# WX0_011_442DL.net
KiCad netlist of a schematic drawn in Altium Designer
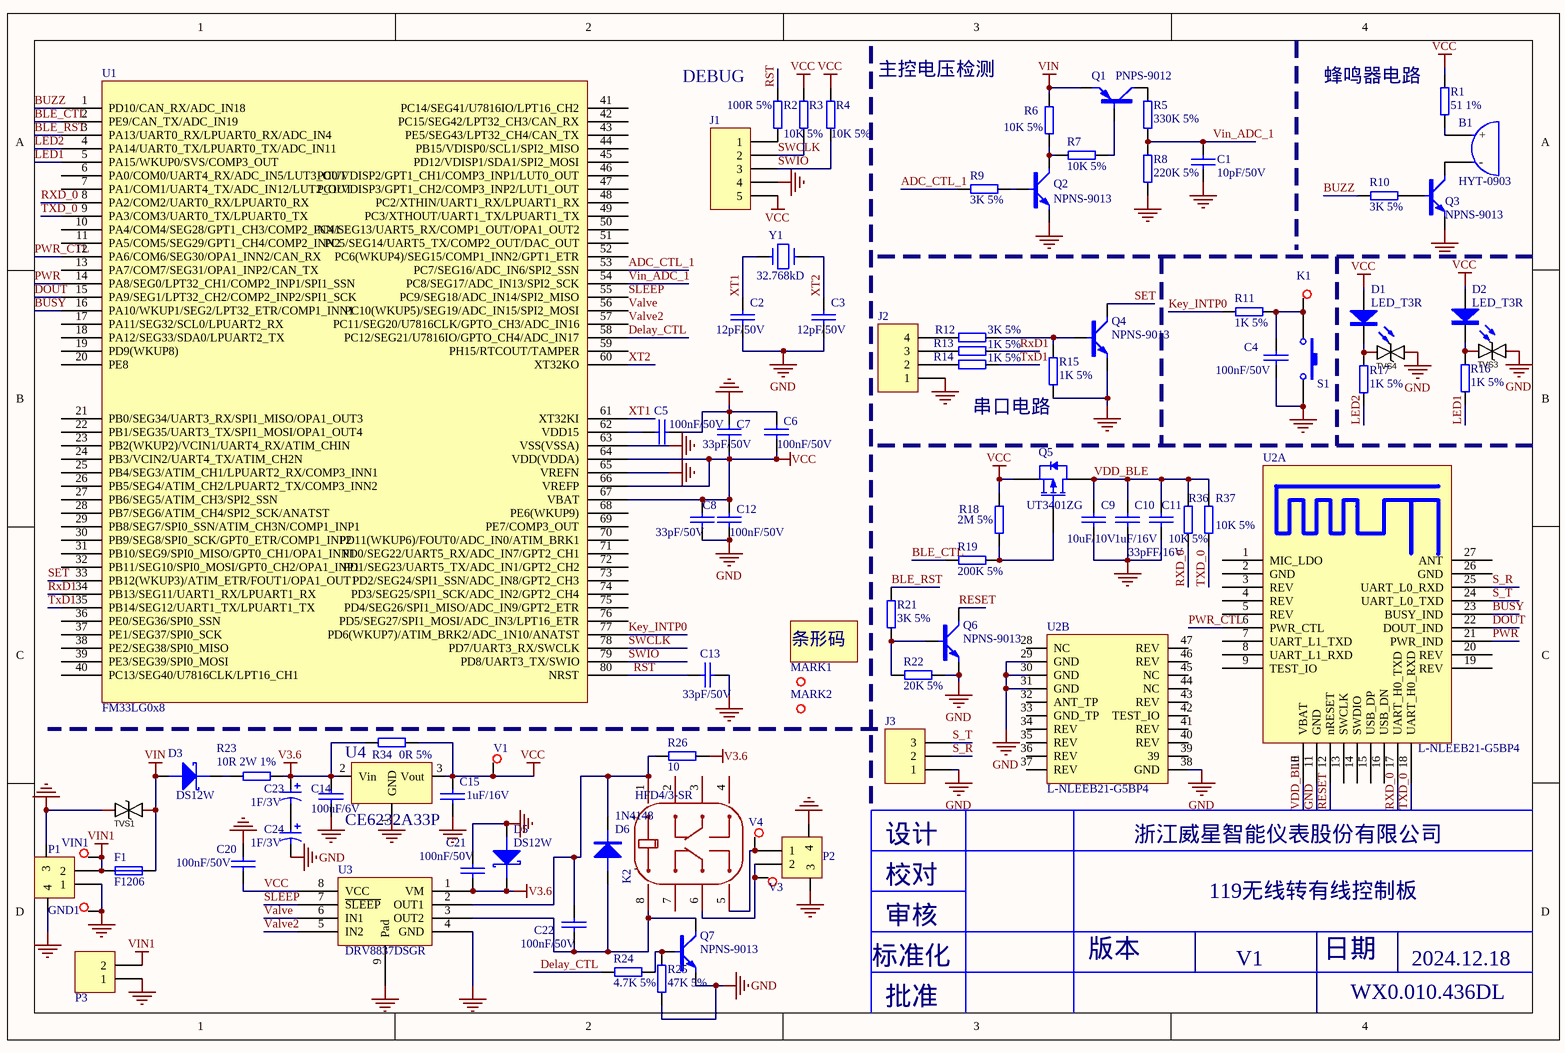
[diagram p0: WX0.011.442DL.SchDoc]

(export (version "E")
  (design (tool "Eeschema 10.0.6"))
  (components
    (comp (ref "*1")
      (value "Bar Code1")
      (footprint "Bar Code1")
      (description "条形码 ,填充，无需焊接器件")
      (fields (field (name "PART NUMBER") "AD_WXHJ_Bar Code_02"))
      (libsource (lib "Database_Libs2") (part "05_AD_WXHJ_Bar Code_02"))
    )
    (comp (ref "B1")
      (value "HYT-0903")
      (footprint "HYT-0903")
      (description "直插,直径9mm,高5.5mm,5 V,2 V,30 mA,兴化市华宇电子有限公司,HYT-0903")
      (fields (field (name "PART NUMBER") "1010602-0007"))
      (libsource (lib "Database_Libs2") (part "07_HYT-0903"))
    )
    (comp (ref "C1")
      (value "10pF/50V")
      (footprint "CAP0603")
      (description "10pF,50 V,±5%,0603,X7R,国巨,CC0603JRNPO9BN100")
      (fields (field (name "PART NUMBER") "101020103-0014"))
      (libsource (lib "Database_Libs2") (part "CC03JPO9_10P"))
    )
    (comp (ref "C2")
      (value "12pF/50V")
      (footprint "CAP0603")
      (description "12P,50 V,±5%,0603,国巨,CC0603JRNPO9BN12")
      (fields (field (name "PART NUMBER") "101020103-0005"))
      (libsource (lib "Database_Libs2") (part "CC03JPO9_12P"))
    )
    (comp (ref "C3")
      (value "12pF/50V")
      (footprint "CAP0603")
      (description "12P,50 V,±5%,0603,国巨,CC0603JRNPO9BN12")
      (fields (field (name "PART NUMBER") "101020103-0005"))
      (libsource (lib "Database_Libs2") (part "CC03JPO9_12P"))
    )
    (comp (ref "C4")
      (value "100nF/50V")
      (footprint "CAP0603")
      (description "104pF,50 V,±10%,0603,国巨,CC0603KRX7R9BB104")
      (fields (field (name "PART NUMBER") "101020103-0021"))
      (libsource (lib "Database_Libs2") (part "CC03K7R9_100N"))
    )
    (comp (ref "C5")
      (value "100nF/50V")
      (footprint "CAP0603")
      (description "104pF,50 V,±10%,0603,国巨,CC0603KRX7R9BB104")
      (fields (field (name "PART NUMBER") "101020103-0021"))
      (libsource (lib "Database_Libs2") (part "CC03K7R9_100N"))
    )
    (comp (ref "C6")
      (value "100nF/50V")
      (footprint "CAP0603")
      (description "104pF,50 V,±10%,0603,国巨,CC0603KRX7R9BB104")
      (fields (field (name "PART NUMBER") "101020103-0021"))
      (libsource (lib "Database_Libs2") (part "CC03K7R9_100N"))
    )
    (comp (ref "C7")
      (value "33pF/50V")
      (footprint "CAP0603")
      (description "33pF,50 V,±10%,0603,国巨,CC0603KRNPO9BN33")
      (fields (field (name "PART NUMBER") "101020103-0027"))
      (libsource (lib "Database_Libs2") (part "CC03KPO9_33P"))
    )
    (comp (ref "C8")
      (value "33pF/50V")
      (footprint "CAP0603")
      (description "33pF,50 V,±10%,0603,国巨,CC0603KRNPO9BN33")
      (fields (field (name "PART NUMBER") "101020103-0027"))
      (libsource (lib "Database_Libs2") (part "CC03KPO9_33P"))
    )
    (comp (ref "C9")
      (value "10uF/10V")
      (footprint "CAP0603")
      (description "106pF,10 V,±10%,0603,村田,GRM188R61A106KE47D")
      (fields (field (name "PART NUMBER") "101020103-0026"))
      (libsource (lib "Database_Libs2") (part "CC03K5R6_10U"))
    )
    (comp (ref "C10")
      (value "1uF/16V")
      (footprint "CAP0603")
      (description "105pF,16 V,±10%,0603,国巨,CC0603KRX7R7BB105")
      (fields (field (name "PART NUMBER") "101020103-0003"))
      (libsource (lib "Database_Libs2") (part "CC03K7R7_1U"))
    )
    (comp (ref "C11")
      (value "33pFF/16V")
      (footprint "CAP0603")
      (description "105pF,16 V,±10%,0603,国巨,CC0603KRX7R7BB105")
      (fields (field (name "PART NUMBER") "101020103-0003"))
      (libsource (lib "Database_Libs2") (part "CC03K7R7_1U"))
    )
    (comp (ref "C12")
      (value "100nF/50V")
      (footprint "CAP0603")
      (description "104pF,50 V,±10%,0603,国巨,CC0603KRX7R9BB104")
      (fields (field (name "PART NUMBER") "101020103-0021"))
      (libsource (lib "Database_Libs2") (part "CC03K7R9_100N"))
    )
    (comp (ref "C13")
      (value "33pF/50V")
      (footprint "CAP0603")
      (description "33pF,50 V,±10%,0603,国巨,CC0603KRNPO9BN33")
      (fields (field (name "PART NUMBER") "101020103-0027"))
      (libsource (lib "Database_Libs2") (part "CC03KPO9_33P"))
    )
    (comp (ref "C14")
      (value "100uF/6V")
      (footprint "GRM1206")
      (description "226P,10 V,±20%,0805,村田电子有限公司,GRM21BR61A226ME51L")
      (fields (field (name "PART NUMBER") "101020102-0012"))
      (libsource (lib "Database_Libs2") (part "CC05M5R6_226P"))
    )
    (comp (ref "C15")
      (value "1uF/16V")
      (footprint "CAP0603")
      (description "105pF,16 V,±10%,0603,国巨,CC0603KRX7R7BB105")
      (fields (field (name "PART NUMBER") "101020103-0003"))
      (libsource (lib "Database_Libs2") (part "CC03K7R7_1U"))
    )
    (comp (ref "C20")
      (value "100nF/50V")
      (footprint "CAP0603")
      (description "104pF,50 V,±10%,0603,国巨,CC0603KRX7R9BB104")
      (fields (field (name "PART NUMBER") "101020103-0021"))
      (libsource (lib "Database_Libs2") (part "CC03K7R9_100N"))
    )
    (comp (ref "C21")
      (value "100nF/50V")
      (footprint "CAP0603")
      (description "104pF,50 V,±10%,0603,国巨,CC0603KRX7R9BB104")
      (fields (field (name "PART NUMBER") "101020103-0021"))
      (libsource (lib "Database_Libs2") (part "CC03K7R9_100N"))
    )
    (comp (ref "C22")
      (value "100nF/50V")
      (footprint "CAP0603")
      (description "104pF,50 V,±10%,0603,国巨,CC0603KRX7R9BB104")
      (fields (field (name "PART NUMBER") "101020103-0021"))
      (libsource (lib "Database_Libs2") (part "CC03K7R9_100N"))
    )
    (comp (ref "C23")
      (value "1F/3V")
      (footprint "CAPPC_350_800_1600R")
      (description "1F,2.75 V,-20%~+20%,8mm*16mm,红宝石,2.7 DMC 1 M MY4 8X16")
      (fields (field (name "PART NUMBER") "1010202-0015"))
      (libsource (lib "Database_Libs2") (part "CALM3MRDMC_1F"))
    )
    (comp (ref "C24")
      (value "1F/3V")
      (footprint "CAPPC_350_800_1600R")
      (description "1F,2.75 V,-20%~+20%,8mm*16mm,红宝石,2.7 DMC 1 M MY4 8X16")
      (fields (field (name "PART NUMBER") "1010202-0015"))
      (libsource (lib "Database_Libs2") (part "CALM3MRDMC_1F"))
    )
    (comp (ref "D1")
      (value "LED_T3R")
      (footprint "LED-SMD-0603 - SMT")
      (description "圆形插件,3mm 圆形,插件,红光,湖北匡通电子有限公司,3BB4HC")
      (fields (field (name "PART NUMBER") "101040102-0001"))
      (libsource (lib "Database_Libs2") (part "01-LED_T3R"))
    )
    (comp (ref "D2")
      (value "LED_T3R")
      (footprint "LED-SMD-0603 - SMT")
      (description "圆形插件,3mm 圆形,插件,红光,湖北匡通电子有限公司,3BB4HC")
      (fields (field (name "PART NUMBER") "101040102-0001"))
      (libsource (lib "Database_Libs2") (part "01-LED_T3R"))
    )
    (comp (ref "D3")
      (value "DS12W")
      (footprint "SOD-123FL")
      (description "DS36W,SOD123-FL,3 A,42 V,60 V,浙江领晨科技有限公司,DS36W")
      (fields (field (name "PART NUMBER") "101040101-0055"))
      (libsource (lib "Database_Libs2") (part "02_DS36W"))
    )
    (comp (ref "D5")
      (value "DS12W")
      (footprint "SOD-123FL")
      (description "DS36W,SOD123-FL,3 A,42 V,60 V,浙江领晨科技有限公司,DS36W")
      (fields (field (name "PART NUMBER") "101040101-0055"))
      (libsource (lib "Database_Libs2") (part "02_DS36W"))
    )
    (comp (ref "D6")
      (value "1N4148")
      (footprint "LL34")
      (description "二极管，Diode")
      (libsource (lib "CBB_Lib_SCH") (part "DIODE"))
    )
    (comp (ref "F1") (value "F1206") (footprint "RES1206") (libsource (lib "Resistor_WX") (part "F1206")))
    (comp (ref "GND1")
      (value "TEST-PAD")
      (footprint "TEST-PAD")
      (description "单面焊盘测试点")
      (fields (field (name "PART NUMBER") "AD_WXHJ_TEST-PAD_01"))
      (libsource (lib "Database_Libs2") (part "TEST-PAD"))
    )
    (comp (ref "J1")
      (value "PIN254_1*5*WXHJ")
      (footprint "PIN254_1*5SR")
      (description "1*5 ，Φ1.0 ，2.54mm，直脚,无需焊接器件")
      (fields (field (name "PART NUMBER") "AD_WXHJ_PinHeader_02"))
      (libsource (lib "Database_Libs2") (part "PIN254_1*5*WXHJ"))
    )
    (comp (ref "J2")
      (value "PIN254_1*4*WXHJ")
      (footprint "PIN254_1*4*1100S")
      (description "1*4 ，Φ1.0 ，2.54mm，直脚,无需焊接器件")
      (fields (field (name "PART NUMBER") "AD_WXHJ_PinHeader_01"))
      (libsource (lib "Database_Libs2") (part "PIN254_1*4*WXHJ"))
    )
    (comp (ref "J3")
      (value "PIN254_1*3")
      (footprint "PIN254_1*3*WXHJ")
      (libsource (lib "Connect_WX") (part "PIN254_1*3"))
    )
    (comp (ref "K1")
      (value "TEST-PAD")
      (footprint "TEST-PAD")
      (description "单面焊盘测试点")
      (fields (field (name "PART NUMBER") "AD_WXHJ_TEST-PAD_01"))
      (libsource (lib "Database_Libs2") (part "TEST-PAD"))
    )
    (comp (ref "K2")
      (value "HFD4/3-SR")
      (footprint "RELAY-SMD_HFD4-XX-SR")
      (fields (field (name "MANUFACTURER") "HF(宏发)"))
      (libsource (lib "altium-import") (part "root_2_mirrored_HFD4/3-SR_"))
    )
    (comp (ref "MARK1")
      (value "MARK")
      (footprint "MARK")
      (description "MARK点")
      (fields (field (name "PART NUMBER") "AD_WXHJ_MARK_01"))
      (libsource (lib "Database_Libs2") (part "MARK"))
    )
    (comp (ref "MARK2")
      (value "MARK")
      (footprint "MARK")
      (description "MARK点")
      (fields (field (name "PART NUMBER") "AD_WXHJ_MARK_01"))
      (libsource (lib "Database_Libs2") (part "MARK"))
    )
    (comp (ref "P1") (value "~") (footprint "2P_2.0mm") (libsource (lib "Connect_WX") (part "SMT_2.0_卧")))
    (comp (ref "P2") (value "~") (libsource (lib "") (part "SMT_2.0_卧_1")))
    (comp (ref "P3")
      (value "PH200_1*2R")
      (footprint "PH200_1*2R_BAT")
      (description "2.0-2AW,直插弯座，2PIN，脚间距2mm，带防翘起,公头,单排,2.0-2AW;直插弯座，2PIN,脚间距2mm，带防翘起")
      (fields (field (name "PART NUMBER") "1010902-0105"))
      (libsource (lib "Free Documents") (part "PH200_1*2R"))
    )
    (comp (ref "Q1")
      (value "PNPS-9012")
      (footprint "SOT-23")
      (description "9012,PNP,SOT-23,JCET;长电,S9012")
      (fields (field (name "PART NUMBER") "101040201-0001"))
      (libsource (lib "Database_Libs2") (part "03_PNPS-9012"))
    )
    (comp (ref "Q2")
      (value "NPNS-9013")
      (footprint "SOT-23")
      (description "9013,NPN,SOT-23,长电,S9013")
      (fields (field (name "PART NUMBER") "101040201-0002"))
      (libsource (lib "Database_Libs2") (part "03_NPNS-9013"))
    )
    (comp (ref "Q3")
      (value "NPNS-9013")
      (footprint "SOT-23")
      (description "9013,NPN,SOT-23,长电,S9013")
      (fields (field (name "PART NUMBER") "101040201-0002"))
      (libsource (lib "Database_Libs2") (part "03_NPNS-9013"))
    )
    (comp (ref "Q4")
      (value "NPNS-9013")
      (footprint "SOT-23")
      (description "9013,NPN,SOT-23,长电,S9013")
      (fields (field (name "PART NUMBER") "101040201-0002"))
      (libsource (lib "Database_Libs2") (part "03_NPNS-9013"))
    )
    (comp (ref "Q5")
      (value "UT3401ZG")
      (footprint "SOT-23")
      (description "UT3401ZG,P-MOS,SOT-23,UTC,UT3401ZG")
      (fields (field (name "PART NUMBER") "101040201-0013"))
      (libsource (lib "Database_Libs2") (part "03_P-UT3401ZG"))
    )
    (comp (ref "Q6")
      (value "NPNS-9013")
      (footprint "SOT-23")
      (description "9013,NPN,SOT-23,长电,S9013")
      (fields (field (name "PART NUMBER") "101040201-0002"))
      (libsource (lib "Database_Libs2") (part "03_NPNS-9013"))
    )
    (comp (ref "Q7")
      (value "NPNS-9013")
      (footprint "SOT-23")
      (description "9013,NPN,SOT-23,长电,S9013")
      (fields (field (name "PART NUMBER") "101040201-0002"))
      (libsource (lib "Database_Libs2") (part "03_NPNS-9013"))
    )
    (comp (ref "R1")
      (value "51 1%")
      (footprint "RES0603")
      (description "国巨,±5%,0603,,155 ℃,-55 ℃,RC0603JR-0751RL,无铅,100 ppm/℃,1/10W,,51欧")
      (fields (field (name "PART NUMBER") "101010103-0037"))
      (libsource (lib "Database_Libs2") (part "RC03J_51R"))
    )
    (comp (ref "R2")
      (value "100R 5%")
      (footprint "RES0603")
      (description "100R,±5%,1/10W,0603,国巨,RC0603JR-07100RL")
      (fields (field (name "PART NUMBER") "101010103-0022"))
      (libsource (lib "Database_Libs2") (part "RC03J_100R"))
    )
    (comp (ref "R3")
      (value "10K 5%")
      (footprint "RES0603")
      (description "国巨,±5%,0603,,155 ℃,-55 ℃,RC0603JR-0710KL,无铅,200 ppm/℃,1/10W,,10K")
      (fields (field (name "PART NUMBER") "101010103-0003"))
      (libsource (lib "Database_Libs2") (part "RC03J_10K"))
    )
    (comp (ref "R4")
      (value "10K 5%")
      (footprint "RES0603")
      (description "国巨,±5%,0603,,155 ℃,-55 ℃,RC0603JR-0710KL,无铅,200 ppm/℃,1/10W,,10K")
      (fields (field (name "PART NUMBER") "101010103-0003"))
      (libsource (lib "Database_Libs2") (part "RC03J_10K"))
    )
    (comp (ref "R5")
      (value "330K 5%")
      (footprint "RES0603")
      (description "330K,±5%,1/10W,0603,国巨,RC0603JR-07330KL")
      (fields (field (name "PART NUMBER") "101010103-0066"))
      (libsource (lib "Database_Libs2") (part "RC03J_330K"))
    )
    (comp (ref "R6")
      (value "10K 5%")
      (footprint "RES0603")
      (description "国巨,±5%,0603,,155 ℃,-55 ℃,RC0603JR-0710KL,无铅,200 ppm/℃,1/10W,,10K")
      (fields (field (name "PART NUMBER") "101010103-0003"))
      (libsource (lib "Database_Libs2") (part "RC03J_10K"))
    )
    (comp (ref "R7")
      (value "10K 5%")
      (footprint "RES0603")
      (description "国巨,±5%,0603,,155 ℃,-55 ℃,RC0603JR-0710KL,无铅,200 ppm/℃,1/10W,,10K")
      (fields (field (name "PART NUMBER") "101010103-0003"))
      (libsource (lib "Database_Libs2") (part "RC03J_10K"))
    )
    (comp (ref "R8")
      (value "220K 5%")
      (footprint "RES0603")
      (description "220K,±5%,1/10W,0603,国巨,RC0603JR-07220KL")
      (fields (field (name "PART NUMBER") "101010103-0044"))
      (libsource (lib "Database_Libs2") (part "RC03J_220K"))
    )
    (comp (ref "R9")
      (value "3K 5%")
      (footprint "RES0603")
      (description "国巨,±5%,0603,,155 ℃,-55 ℃,RC0603JR-073KL,无铅,100 ppm/℃,1/10W,,3K")
      (fields (field (name "PART NUMBER") "101010103-0006"))
      (libsource (lib "Database_Libs2") (part "RC03J_3K"))
    )
    (comp (ref "R10")
      (value "3K 5%")
      (footprint "RES0603")
      (description "国巨,±5%,0603,,155 ℃,-55 ℃,RC0603JR-073KL,无铅,100 ppm/℃,1/10W,,3K")
      (fields (field (name "PART NUMBER") "101010103-0006"))
      (libsource (lib "Database_Libs2") (part "RC03J_3K"))
    )
    (comp (ref "R11")
      (value "1K 5%")
      (footprint "RES0603")
      (description "国巨,±5%,0603,,155 ℃,-55 ℃,RC0603JR-073KL,无铅,100 ppm/℃,1/10W,,3K")
      (fields (field (name "PART NUMBER") "101010103-0006"))
      (libsource (lib "Database_Libs2") (part "RC03J_3K"))
    )
    (comp (ref "R12")
      (value "3K 5%")
      (description "国巨,±5%,0603,,155 ℃,-55 ℃,RC0603JR-073KL,无铅,100 ppm/℃,1/10W,,3K")
      (fields (field (name "PART NUMBER") "101010103-0006"))
      (libsource (lib "Database_Libs2") (part "RC03J_3K"))
    )
    (comp (ref "R13")
      (value "1K 5%")
      (footprint "RES0603")
      (description "1K,±5%,1/10W,0603,国巨,RC0603JR-071KL")
      (fields (field (name "PART NUMBER") "101010103-0008"))
      (libsource (lib "Database_Libs2") (part "RC03J_1K"))
    )
    (comp (ref "R14")
      (value "1K 5%")
      (footprint "RES0603")
      (description "1K,±5%,1/10W,0603,国巨,RC0603JR-071KL")
      (fields (field (name "PART NUMBER") "101010103-0008"))
      (libsource (lib "Database_Libs2") (part "RC03J_1K"))
    )
    (comp (ref "R15")
      (value "1K 5%")
      (footprint "RES0603")
      (description "1K,±5%,1/10W,0603,国巨,RC0603JR-071KL")
      (fields (field (name "PART NUMBER") "101010103-0008"))
      (libsource (lib "Database_Libs2") (part "RC03J_1K"))
    )
    (comp (ref "R16")
      (value "1K 5%")
      (footprint "RES0603")
      (description "1K,±5%,1/10W,0603,国巨,RC0603JR-071KL")
      (fields (field (name "PART NUMBER") "101010103-0008"))
      (libsource (lib "Database_Libs2") (part "RC03J_1K"))
    )
    (comp (ref "R17")
      (value "1K 5%")
      (footprint "RES0603")
      (description "1K,±5%,1/10W,0603,国巨,RC0603JR-071KL")
      (fields (field (name "PART NUMBER") "101010103-0008"))
      (libsource (lib "Database_Libs2") (part "RC03J_1K"))
    )
    (comp (ref "R18")
      (value "2M 5%")
      (footprint "RES0603")
      (description "国巨,±5%,0603,,155 ℃,-55 ℃,RC0603JR-072ML,含铅,100 ppm/℃,1/10W,,2M")
      (fields (field (name "PART NUMBER") "101010103-0025"))
      (libsource (lib "Database_Libs2") (part "RC03J_2M"))
    )
    (comp (ref "R19")
      (value "200K 5%")
      (footprint "RES0603")
      (description "10K±5%,1/10W,0603")
      (fields (field (name "PART NUMBER") "101010103-0003"))
      (libsource (lib "Database_Libs1") (part "RC03JF_10K"))
    )
    (comp (ref "R21")
      (value "3K 5%")
      (footprint "RES0603")
      (description "国巨,±5%,0603,,155 ℃,-55 ℃,RC0603JR-073KL,无铅,100 ppm/℃,1/10W,,3K")
      (fields (field (name "PART NUMBER") "101010103-0006"))
      (libsource (lib "Database_Libs2") (part "RC03J_3K"))
    )
    (comp (ref "R22")
      (value "20K 5%")
      (footprint "RES0603")
      (description "国巨,±5%,0603,,155 ℃,-55 ℃,RC0603JR-0720KL,无铅,200 ppm/℃,1/10W,,20K")
      (fields (field (name "PART NUMBER") "101010103-0004"))
      (libsource (lib "Database_Libs2") (part "RC03J_20K"))
    )
    (comp (ref "R23")
      (value "10R 2W 1%")
      (footprint "RES2512")
      (description "0.5Ω,±1%,1W,2512,国巨,RC2512FR-070R5L")
      (fields (field (name "PART NUMBER") "101010105-0001"))
      (libsource (lib "Database_Libs2") (part "RES_0R5"))
    )
    (comp (ref "R24")
      (value "4.7K 5%")
      (footprint "RES0603")
      (description "国巨,±5%,0603,,155 ℃,-55 ℃,RC0603JR-073KL,无铅,100 ppm/℃,1/10W,,3K")
      (fields (field (name "PART NUMBER") "101010103-0006"))
      (libsource (lib "Database_Libs2") (part "RC03J_3K"))
    )
    (comp (ref "R25")
      (value "47K 5%")
      (footprint "RES0603")
      (description "国巨,±5%,0603,,155 ℃,-55 ℃,RC0603JR-0720KL,无铅,200 ppm/℃,1/10W,,20K")
      (fields (field (name "PART NUMBER") "101010103-0004"))
      (libsource (lib "Database_Libs2") (part "RC03J_20K"))
    )
    (comp (ref "R26")
      (value "10")
      (footprint "RES0603")
      (description "国巨,±5%,0603,,155 ℃,-55 ℃,RC0603JR-073KL,无铅,100 ppm/℃,1/10W,,3K")
      (fields (field (name "PART NUMBER") "101010103-0006"))
      (libsource (lib "Database_Libs2") (part "RC03J_3K"))
    )
    (comp (ref "R34")
      (value "0R 5%")
      (footprint "RES1206")
      (description "1K,±5%,1/10W,0603,国巨,RC0603JR-071KL")
      (fields (field (name "PART NUMBER") "101010103-0008"))
      (libsource (lib "Database_Libs2") (part "RC03J_1K"))
    )
    (comp (ref "R36")
      (value "10K 5%")
      (footprint "RES0603")
      (description "国巨,±5%,0603,,155 ℃,-55 ℃,RC0603JR-0710KL,无铅,200 ppm/℃,1/10W,,10K")
      (fields (field (name "PART NUMBER") "101010103-0003"))
      (libsource (lib "Database_Libs2") (part "RC03J_10K"))
    )
    (comp (ref "R37")
      (value "10K 5%")
      (footprint "RES0603")
      (description "国巨,±5%,0603,,155 ℃,-55 ℃,RC0603JR-0710KL,无铅,200 ppm/℃,1/10W,,10K")
      (fields (field (name "PART NUMBER") "101010103-0003"))
      (libsource (lib "Database_Libs2") (part "RC03J_10K"))
    )
    (comp (ref "S1")
      (value "SWT_4_600_600_430")
      (footprint "SWS_4_600_600")
      (description "TS-1102,机械轻触,6*6*4.3直插,6*6*4.3直插,乐清市羽欧电子")
      (fields (field (name "PART NUMBER") "1011001-0027"))
      (libsource (lib "Database_Libs2") (part "07_SWT_4_600_600_430"))
    )
    (comp (ref "TVS1")
      (value "~")
      (footprint "DO-214AA")
      (fields (field (name "MANUFACTURER") "AnBon(台湾安邦)") (field (name "MANUFACTURER PART") "SMBJ12CA"))
      (libsource (lib "Schlib1") (part "SMBJ12CA"))
    )
    (comp (ref "TVS3")
      (value "~")
      (footprint "ESD_DFN1006_2L")
      (fields (field (name "MANUFACTURER") "AnBon(台湾安邦)") (field (name "MANUFACTURER PART") "SMBJ12CA"))
      (libsource (lib "Schlib1") (part "SMBJ12CA"))
    )
    (comp (ref "TVS4")
      (value "~")
      (footprint "ESD_DFN1006_2L")
      (fields (field (name "MANUFACTURER") "AnBon(台湾安邦)") (field (name "MANUFACTURER PART") "SMBJ12CA"))
      (libsource (lib "Schlib1") (part "SMBJ12CA"))
    )
    (comp (ref "U1") (value "FM33LG0x8") (footprint "LQFP80") (libsource (lib "FM_MCU") (part "FM33LG0x8")))
    (comp (ref "U2")
      (value "L-NLEEB21-G5BP4")
      (footprint "L-NLEEB21-G5BP4")
      (libsource (lib "Mixed_WX") (part "L-NLEEB21-G5BP4"))
    )
    (comp (ref "U3")
      (value "DRV8837DSGR")
      (footprint "S-PWSON-N8")
      (description "DRV8837DSGR,S-PWSON-N8,TI,DRV8837DSGR")
      (fields (field (name "PART NUMBER") "101050101-0060"))
      (libsource (lib "Database_Libs2") (part "07_DRV8837DSGR"))
    )
    (comp (ref "U4")
      (value "CE6232A33P")
      (footprint "SOT-89")
      (libsource (lib "Chip_WX") (part "02_CE6232A33P"))
    )
    (comp (ref "V1")
      (value "TEST-PAD")
      (footprint "TEST-PAD")
      (description "单面焊盘测试点")
      (fields (field (name "PART NUMBER") "AD_WXHJ_TEST-PAD_01"))
      (libsource (lib "Database_Libs2") (part "TEST-PAD"))
    )
    (comp (ref "V3")
      (value "TEST-PAD")
      (footprint "TEST-PAD")
      (description "单面焊盘测试点")
      (fields (field (name "PART NUMBER") "AD_WXHJ_TEST-PAD_01"))
      (libsource (lib "Database_Libs2") (part "TEST-PAD"))
    )
    (comp (ref "V4")
      (value "TEST-PAD")
      (footprint "TEST-PAD")
      (description "单面焊盘测试点")
      (fields (field (name "PART NUMBER") "AD_WXHJ_TEST-PAD_01"))
      (libsource (lib "Database_Libs2") (part "TEST-PAD"))
    )
    (comp (ref "VIN1")
      (value "TEST-PAD")
      (footprint "TEST-PAD")
      (description "单面焊盘测试点")
      (fields (field (name "PART NUMBER") "AD_WXHJ_TEST-PAD_01"))
      (libsource (lib "Database_Libs2") (part "TEST-PAD"))
    )
    (comp (ref "Y1")
      (value "32.768kD")
      (footprint "SMD-3215_2P")
      (fields (field (name "PART NUMBER") "1010601-0020"))
      (libsource (lib "Database_Libs2") (part "04_XTALSG12MD_32.768kD"))
    )
  )
  (nets
    (net (code "1") (name "/ADC_CTL_1") (class "Default")
      (node (ref "R9") (pin "1") (pinfunction "1_1") (pintype "passive"))
      (node (ref "U1") (pin "53") (pinfunction "PC7/SEG16/ADC_IN6/SPI2_SSN_53") (pintype "passive"))
    )
    (net (code "2") (name "/BLE_CTL") (class "Default")
      (node (ref "R19") (pin "1") (pinfunction "1_1") (pintype "passive"))
      (node (ref "U1") (pin "2") (pinfunction "PE9/CAN_TX/ADC_IN19_2") (pintype "passive"))
    )
    (net (code "3") (name "/BLE_RST") (class "Default")
      (node (ref "R21") (pin "1") (pinfunction "1_1") (pintype "passive"))
      (node (ref "U1") (pin "3") (pinfunction "PA13/UART0_RX/LPUART0_RX/ADC_IN4_3") (pintype "passive"))
    )
    (net (code "4") (name "/BUSY") (class "Default")
      (node (ref "U1") (pin "16") (pinfunction "PA10/WKUP1/SEG2/LPT32_ETR/COMP1_INN1_16") (pintype "passive"))
      (node (ref "U2") (pin "23") (pinfunction "BUSY_IND_23") (pintype "passive"))
    )
    (net (code "5") (name "/BUZZ") (class "Default")
      (node (ref "R10") (pin "1") (pinfunction "1_1") (pintype "passive"))
      (node (ref "U1") (pin "1") (pinfunction "PD10/CAN_RX/ADC_IN18_1") (pintype "passive"))
    )
    (net (code "6") (name "/DOUT") (class "Default")
      (node (ref "U1") (pin "15") (pinfunction "PA9/SEG1/LPT32_CH2/COMP2_INP2/SPI1_SCK_15") (pintype "passive"))
      (node (ref "U2") (pin "22") (pinfunction "DOUT_IND_22") (pintype "passive"))
    )
    (net (code "7") (name "/Delay_CTL") (class "Default")
      (node (ref "R24") (pin "1") (pinfunction "1_1") (pintype "passive"))
      (node (ref "U1") (pin "58") (pinfunction "PC12/SEG21/U7816IO/GPTO_CH4/ADC_IN17_58") (pintype "passive"))
    )
    (net (code "8") (name "/Key_INTP0") (class "Default")
      (node (ref "R11") (pin "2") (pinfunction "2_2") (pintype "passive"))
      (node (ref "U1") (pin "77") (pinfunction "PD6(WKUP7)/ATIM_BRK2/ADC_1N10/ANATST_77") (pintype "passive"))
    )
    (net (code "9") (name "/LED1") (class "Default")
      (node (ref "R16") (pin "1") (pinfunction "1_1") (pintype "passive"))
      (node (ref "U1") (pin "5") (pinfunction "PA15/WKUP0/SVS/COMP3_OUT_5") (pintype "passive"))
    )
    (net (code "10") (name "/LED2") (class "Default")
      (node (ref "R17") (pin "1") (pinfunction "1_1") (pintype "passive"))
      (node (ref "U1") (pin "4") (pinfunction "PA14/UART0_TX/LPUART0_TX/ADC_IN11_4") (pintype "passive"))
    )
    (net (code "11") (name "/PWR") (class "Default")
      (node (ref "U1") (pin "14") (pinfunction "PA8/SEG0/LPT32_CH1/COMP2_INP1/SPI1_SSN_14") (pintype "passive"))
      (node (ref "U2") (pin "21") (pinfunction "PWR_IND_21") (pintype "passive"))
    )
    (net (code "12") (name "/PWR_CTL") (class "Default")
      (node (ref "U1") (pin "12") (pinfunction "PA6/COM6/SEG30/OPA1_INN2/CAN_RX_12") (pintype "passive"))
      (node (ref "U2") (pin "6") (pinfunction "PWR_CTL_6") (pintype "passive"))
    )
    (net (code "13") (name "/RESET") (class "Default")
      (node (ref "Q6") (pin "3") (pinfunction "C_3") (pintype "passive"))
      (node (ref "U2") (pin "12") (pinfunction "nRESET_12") (pintype "passive"))
    )
    (net (code "14") (name "/RST") (class "Default")
      (node (ref "C13") (pin "1") (pinfunction "1_1") (pintype "passive"))
      (node (ref "R2") (pin "1") (pinfunction "1_1") (pintype "passive"))
      (node (ref "U1") (pin "80") (pinfunction "NRST_80") (pintype "passive"))
    )
    (net (code "15") (name "/RXD_0") (class "Default")
      (node (ref "R36") (pin "2") (pinfunction "2_2") (pintype "passive"))
      (node (ref "U1") (pin "8") (pinfunction "PA2/COM2/UART0_RX/LPUART0_RX_8") (pintype "passive"))
      (node (ref "U2") (pin "17") (pinfunction "UART_H0_TXD_17") (pintype "passive"))
    )
    (net (code "16") (name "/RxD1") (class "Default")
      (node (ref "R13") (pin "2") (pinfunction "2_2") (pintype "passive"))
      (node (ref "U1") (pin "34") (pinfunction "PB13/SEG11/UART1_RX/LPUART1_RX_34") (pintype "passive"))
    )
    (net (code "17") (name "/SET") (class "Default")
      (node (ref "Q4") (pin "3") (pinfunction "C_3") (pintype "passive"))
      (node (ref "U1") (pin "33") (pinfunction "PB12(WKUP3)/ATIM_ETR/FOUT1/OPA1_OUT1_33") (pintype "passive"))
    )
    (net (code "18") (name "/SLEEP") (class "Default")
      (node (ref "U1") (pin "55") (pinfunction "PC9/SEG18/ADC_IN14/SPI2_MISO_55") (pintype "passive"))
      (node (ref "U3") (pin "7") (pinfunction "~{SLEEP}_7") (pintype "passive"))
    )
    (net (code "19") (name "/SWCLK") (class "Default")
      (node (ref "J1") (pin "2") (pinfunction "2_2") (pintype "passive"))
      (node (ref "R3") (pin "2") (pinfunction "2_2") (pintype "passive"))
      (node (ref "U1") (pin "78") (pinfunction "PD7/UART3_RX/SWCLK_78") (pintype "passive"))
    )
    (net (code "20") (name "/SWIO") (class "Default")
      (node (ref "J1") (pin "3") (pinfunction "3_3") (pintype "passive"))
      (node (ref "R4") (pin "2") (pinfunction "2_2") (pintype "passive"))
      (node (ref "U1") (pin "79") (pinfunction "PD8/UART3_TX/SWIO_79") (pintype "passive"))
    )
    (net (code "21") (name "/S_R") (class "Default")
      (node (ref "J3") (pin "2") (pinfunction "2_2") (pintype "passive"))
      (node (ref "U2") (pin "25") (pinfunction "UART_L0_RXD_25") (pintype "passive"))
    )
    (net (code "22") (name "/S_T") (class "Default")
      (node (ref "J3") (pin "3") (pinfunction "3_3") (pintype "passive"))
      (node (ref "U2") (pin "24") (pinfunction "UART_L0_TXD_24") (pintype "passive"))
    )
    (net (code "23") (name "/TXD_0") (class "Default")
      (node (ref "R37") (pin "2") (pinfunction "2_2") (pintype "passive"))
      (node (ref "U1") (pin "9") (pinfunction "PA3/COM3/UART0_TX/LPUART0_TX_9") (pintype "passive"))
      (node (ref "U2") (pin "18") (pinfunction "UART_H0_RXD_18") (pintype "passive"))
    )
    (net (code "24") (name "/TxD1") (class "Default")
      (node (ref "R14") (pin "2") (pinfunction "2_2") (pintype "passive"))
      (node (ref "U1") (pin "35") (pinfunction "PB14/SEG12/UART1_TX/LPUART1_TX_35") (pintype "passive"))
    )
    (net (code "25") (name "/VDD_BLE") (class "Default")
      (node (ref "C10") (pin "1") (pinfunction "1_1") (pintype "passive"))
      (node (ref "C11") (pin "1") (pinfunction "1_1") (pintype "passive"))
      (node (ref "C9") (pin "1") (pinfunction "1_1") (pintype "passive"))
      (node (ref "Q5") (pin "3") (pinfunction "D_3") (pintype "passive"))
      (node (ref "R36") (pin "1") (pinfunction "1_1") (pintype "passive"))
      (node (ref "R37") (pin "1") (pinfunction "1_1") (pintype "passive"))
      (node (ref "U2") (pin "10") (pinfunction "VBAT_10") (pintype "passive"))
    )
    (net (code "26") (name "/Valve") (class "Default")
      (node (ref "U1") (pin "56") (pinfunction "PC10(WKUP5)/SEG19/ADC_IN15/SPI2_MOSI_56") (pintype "passive"))
      (node (ref "U3") (pin "6") (pinfunction "IN1_6") (pintype "passive"))
    )
    (net (code "27") (name "/Valve2") (class "Default")
      (node (ref "U1") (pin "57") (pinfunction "PC11/SEG20/U7816CLK/GPTO_CH3/ADC_IN16_57") (pintype "passive"))
      (node (ref "U3") (pin "5") (pinfunction "IN2_5") (pintype "passive"))
    )
    (net (code "28") (name "/Vin_ADC_1") (class "Default")
      (node (ref "C1") (pin "2") (pinfunction "2_2") (pintype "passive"))
      (node (ref "R5") (pin "2") (pinfunction "2_2") (pintype "passive"))
      (node (ref "R8") (pin "1") (pinfunction "1_1") (pintype "passive"))
      (node (ref "U1") (pin "54") (pinfunction "PC8/SEG17/ADC_IN13/SPI2_SCK_54") (pintype "passive"))
    )
    (net (code "29") (name "/XT1") (class "Default")
      (node (ref "C2") (pin "1") (pinfunction "1_1") (pintype "passive"))
      (node (ref "U1") (pin "61") (pinfunction "XT32KI_61") (pintype "passive"))
      (node (ref "Y1") (pin "1") (pinfunction "1_1") (pintype "passive"))
    )
    (net (code "30") (name "/XT2") (class "Default")
      (node (ref "C3") (pin "2") (pinfunction "2_2") (pintype "passive"))
      (node (ref "U1") (pin "60") (pinfunction "XT32KO_60") (pintype "passive"))
      (node (ref "Y1") (pin "2") (pinfunction "2_2") (pintype "passive"))
    )
    (net (code "31") (name "GND") (class "Default")
      (node (ref "C1") (pin "1") (pinfunction "1_1") (pintype "passive"))
      (node (ref "C10") (pin "2") (pinfunction "2_2") (pintype "passive"))
      (node (ref "C11") (pin "2") (pinfunction "2_2") (pintype "passive"))
      (node (ref "C12") (pin "2") (pinfunction "2_2") (pintype "passive"))
      (node (ref "C13") (pin "2") (pinfunction "2_2") (pintype "passive"))
      (node (ref "C14") (pin "2") (pinfunction "2_2") (pintype "passive"))
      (node (ref "C15") (pin "2") (pinfunction "2_2") (pintype "passive"))
      (node (ref "C2") (pin "2") (pinfunction "2_2") (pintype "passive"))
      (node (ref "C20") (pin "1") (pinfunction "1_1") (pintype "passive"))
      (node (ref "C21") (pin "2") (pinfunction "2_2") (pintype "passive"))
      (node (ref "C24") (pin "2") (pinfunction "2_2") (pintype "passive"))
      (node (ref "C3") (pin "1") (pinfunction "1_1") (pintype "passive"))
      (node (ref "C4") (pin "2") (pinfunction "2_2") (pintype "passive"))
      (node (ref "C5") (pin "2") (pinfunction "2_2") (pintype "passive"))
      (node (ref "C6") (pin "1") (pinfunction "1_1") (pintype "passive"))
      (node (ref "C7") (pin "1") (pinfunction "1_1") (pintype "passive"))
      (node (ref "C8") (pin "2") (pinfunction "2_2") (pintype "passive"))
      (node (ref "C9") (pin "2") (pinfunction "2_2") (pintype "passive"))
      (node (ref "D5") (pin "1") (pinfunction "1_1") (pintype "passive"))
      (node (ref "GND1") (pin "1") (pinfunction "1_1") (pintype "passive"))
      (node (ref "J1") (pin "4") (pinfunction "4_4") (pintype "passive"))
      (node (ref "J2") (pin "1") (pinfunction "1_1") (pintype "passive"))
      (node (ref "J3") (pin "1") (pinfunction "1_1") (pintype "passive"))
      (node (ref "P1") (pin "1") (pinfunction "1_1") (pintype "passive"))
      (node (ref "P1") (pin "3") (pinfunction "3_3") (pintype "passive"))
      (node (ref "P1") (pin "4") (pinfunction "4_4") (pintype "passive"))
      (node (ref "P2") (pin "3") (pinfunction "3_3") (pintype "passive"))
      (node (ref "P2") (pin "4") (pinfunction "4_4") (pintype "passive"))
      (node (ref "P3") (pin "1") (pinfunction "1_1") (pintype "passive"))
      (node (ref "Q2") (pin "2") (pinfunction "E_2") (pintype "passive"))
      (node (ref "Q3") (pin "2") (pinfunction "E_2") (pintype "passive"))
      (node (ref "Q4") (pin "2") (pinfunction "E_2") (pintype "passive"))
      (node (ref "Q6") (pin "2") (pinfunction "E_2") (pintype "passive"))
      (node (ref "Q7") (pin "2") (pinfunction "E_2") (pintype "passive"))
      (node (ref "R15") (pin "1") (pinfunction "1_1") (pintype "passive"))
      (node (ref "R22") (pin "2") (pinfunction "2_2") (pintype "passive"))
      (node (ref "R25") (pin "1") (pinfunction "1_1") (pintype "passive"))
      (node (ref "R8") (pin "2") (pinfunction "2_2") (pintype "passive"))
      (node (ref "S1") (pin "2") (pinfunction "2_2") (pintype "passive"))
      (node (ref "TVS1") (pin "1") (pinfunction "1_1") (pintype "passive"))
      (node (ref "TVS3") (pin "1") (pinfunction "1_1") (pintype "passive"))
      (node (ref "TVS4") (pin "1") (pinfunction "1_1") (pintype "passive"))
      (node (ref "U1") (pin "63") (pinfunction "VSS(VSSA)_63") (pintype "passive"))
      (node (ref "U1") (pin "65") (pinfunction "VREFN_65") (pintype "passive"))
      (node (ref "U2") (pin "11") (pinfunction "GND_11") (pintype "passive"))
      (node (ref "U2") (pin "29") (pinfunction "GND_29") (pintype "passive"))
      (node (ref "U2") (pin "30") (pinfunction "GND_30") (pintype "passive"))
      (node (ref "U2") (pin "31") (pinfunction "GND_31") (pintype "passive"))
      (node (ref "U2") (pin "38") (pinfunction "GND_38") (pintype "passive"))
      (node (ref "U3") (pin "4") (pinfunction "GND_4") (pintype "passive"))
      (node (ref "U3") (pin "9") (pinfunction "Pad_9") (pintype "passive"))
      (node (ref "U4") (pin "1") (pinfunction "GND_1") (pintype "passive"))
    )
    (net (code "32") (name "Net-(B1-+)") (class "Default")
      (node (ref "B1") (pin "1") (pinfunction "+_1") (pintype "passive"))
      (node (ref "R1") (pin "1") (pinfunction "1_1") (pintype "passive"))
    )
    (net (code "33") (name "Net-(B1--)") (class "Default")
      (node (ref "B1") (pin "2") (pinfunction "-_2") (pintype "passive"))
      (node (ref "Q3") (pin "3") (pinfunction "C_3") (pintype "passive"))
    )
    (net (code "34") (name "Net-(C4-Pad1)") (class "Default")
      (node (ref "C4") (pin "1") (pinfunction "1_1") (pintype "passive"))
      (node (ref "K1") (pin "1") (pinfunction "1_1") (pintype "passive"))
      (node (ref "R11") (pin "1") (pinfunction "1_1") (pintype "passive"))
      (node (ref "S1") (pin "1") (pinfunction "1_1") (pintype "passive"))
    )
    (net (code "35") (name "Net-(C23-Pad2)") (class "Default")
      (node (ref "C23") (pin "2") (pinfunction "2_2") (pintype "passive"))
      (node (ref "C24") (pin "1") (pinfunction "1_1") (pintype "passive"))
    )
    (net (code "36") (name "Net-(D1-Pad2)") (class "Default")
      (node (ref "D1") (pin "2") (pinfunction "2_2") (pintype "passive"))
      (node (ref "R17") (pin "2") (pinfunction "2_2") (pintype "passive"))
      (node (ref "TVS4") (pin "2") (pinfunction "2_2") (pintype "passive"))
    )
    (net (code "37") (name "Net-(D2-Pad2)") (class "Default")
      (node (ref "D2") (pin "2") (pinfunction "2_2") (pintype "passive"))
      (node (ref "R16") (pin "2") (pinfunction "2_2") (pintype "passive"))
      (node (ref "TVS3") (pin "2") (pinfunction "2_2") (pintype "passive"))
    )
    (net (code "38") (name "Net-(D3-Pad2)") (class "Default")
      (node (ref "D3") (pin "2") (pinfunction "2_2") (pintype "passive"))
      (node (ref "R23") (pin "1") (pinfunction "1_1") (pintype "passive"))
    )
    (net (code "39") (name "Net-(D6-A)") (class "Default")
      (node (ref "C22") (pin "2") (pinfunction "2_2") (pintype "passive"))
      (node (ref "D6") (pin "1") (pinfunction "A_1") (pintype "passive"))
      (node (ref "K2") (pin "8") (pinfunction "8_8") (pintype "passive"))
      (node (ref "Q7") (pin "3") (pinfunction "C_3") (pintype "passive"))
      (node (ref "U3") (pin "3") (pinfunction "OUT2_3") (pintype "passive"))
    )
    (net (code "40") (name "Net-(D6-K)") (class "Default")
      (node (ref "C22") (pin "1") (pinfunction "1_1") (pintype "passive"))
      (node (ref "D6") (pin "2") (pinfunction "K_2") (pintype "passive"))
      (node (ref "K2") (pin "1") (pinfunction "1_1") (pintype "passive"))
      (node (ref "R26") (pin "1") (pinfunction "1_1") (pintype "passive"))
      (node (ref "U3") (pin "2") (pinfunction "OUT1_2") (pintype "passive"))
    )
    (net (code "41") (name "Net-(J1-Pad1)") (class "Default")
      (node (ref "J1") (pin "1") (pinfunction "1_1") (pintype "passive"))
      (node (ref "R2") (pin "2") (pinfunction "2_2") (pintype "passive"))
    )
    (net (code "42") (name "Net-(J2-Pad2)") (class "Default")
      (node (ref "J2") (pin "2") (pinfunction "2_2") (pintype "passive"))
      (node (ref "R14") (pin "1") (pinfunction "1_1") (pintype "passive"))
    )
    (net (code "43") (name "Net-(J2-Pad3)") (class "Default")
      (node (ref "J2") (pin "3") (pinfunction "3_3") (pintype "passive"))
      (node (ref "R13") (pin "1") (pinfunction "1_1") (pintype "passive"))
    )
    (net (code "44") (name "Net-(J2-Pad4)") (class "Default")
      (node (ref "J2") (pin "4") (pinfunction "4_4") (pintype "passive"))
      (node (ref "R12") (pin "1") (pinfunction "1_1") (pintype "passive"))
    )
    (net (code "45") (name "Net-(K2-Pad5)") (class "Default")
      (node (ref "K2") (pin "5") (pinfunction "5_5") (pintype "passive"))
      (node (ref "P2") (pin "1") (pinfunction "1_1") (pintype "passive"))
      (node (ref "V4") (pin "1") (pinfunction "1_1") (pintype "passive"))
    )
    (net (code "46") (name "Net-(K2-Pad6)") (class "Default")
      (node (ref "K2") (pin "6") (pinfunction "6_6") (pintype "passive"))
      (node (ref "P2") (pin "2") (pinfunction "2_2") (pintype "passive"))
      (node (ref "V3") (pin "1") (pinfunction "1_1") (pintype "passive"))
    )
    (net (code "47") (name "Net-(Q1-B)") (class "Default")
      (node (ref "Q1") (pin "1") (pinfunction "B_1") (pintype "passive"))
      (node (ref "R7") (pin "2") (pinfunction "2_2") (pintype "passive"))
    )
    (net (code "48") (name "Net-(Q1-C)") (class "Default")
      (node (ref "Q1") (pin "3") (pinfunction "C_3") (pintype "passive"))
      (node (ref "R5") (pin "1") (pinfunction "1_1") (pintype "passive"))
    )
    (net (code "49") (name "Net-(Q2-B)") (class "Default")
      (node (ref "Q2") (pin "1") (pinfunction "B_1") (pintype "passive"))
      (node (ref "R9") (pin "2") (pinfunction "2_2") (pintype "passive"))
    )
    (net (code "50") (name "Net-(Q2-C)") (class "Default")
      (node (ref "Q2") (pin "3") (pinfunction "C_3") (pintype "passive"))
      (node (ref "R6") (pin "1") (pinfunction "1_1") (pintype "passive"))
      (node (ref "R7") (pin "1") (pinfunction "1_1") (pintype "passive"))
    )
    (net (code "51") (name "Net-(Q3-B)") (class "Default")
      (node (ref "Q3") (pin "1") (pinfunction "B_1") (pintype "passive"))
      (node (ref "R10") (pin "2") (pinfunction "2_2") (pintype "passive"))
    )
    (net (code "52") (name "Net-(Q4-B)") (class "Default")
      (node (ref "Q4") (pin "1") (pinfunction "B_1") (pintype "passive"))
      (node (ref "R12") (pin "2") (pinfunction "2_2") (pintype "passive"))
      (node (ref "R15") (pin "2") (pinfunction "2_2") (pintype "passive"))
    )
    (net (code "53") (name "Net-(Q5-G)") (class "Default")
      (node (ref "Q5") (pin "1") (pinfunction "G_1") (pintype "passive"))
      (node (ref "R18") (pin "1") (pinfunction "1_1") (pintype "passive"))
      (node (ref "R19") (pin "2") (pinfunction "2_2") (pintype "passive"))
    )
    (net (code "54") (name "Net-(Q6-B)") (class "Default")
      (node (ref "Q6") (pin "1") (pinfunction "B_1") (pintype "passive"))
      (node (ref "R21") (pin "2") (pinfunction "2_2") (pintype "passive"))
      (node (ref "R22") (pin "1") (pinfunction "1_1") (pintype "passive"))
    )
    (net (code "55") (name "Net-(Q7-B)") (class "Default")
      (node (ref "Q7") (pin "1") (pinfunction "B_1") (pintype "passive"))
      (node (ref "R24") (pin "2") (pinfunction "2_2") (pintype "passive"))
      (node (ref "R25") (pin "2") (pinfunction "2_2") (pintype "passive"))
    )
    (net (code "56") (name "Net-(U1-VDD15)") (class "Default")
      (node (ref "C5") (pin "1") (pinfunction "1_1") (pintype "passive"))
      (node (ref "U1") (pin "62") (pinfunction "VDD15_62") (pintype "passive"))
    )
    (net (code "57") (name "V3.6") (class "Default")
      (node (ref "C14") (pin "1") (pinfunction "1_1") (pintype "passive"))
      (node (ref "C21") (pin "1") (pinfunction "1_1") (pintype "passive"))
      (node (ref "C23") (pin "1") (pinfunction "1_1") (pintype "passive"))
      (node (ref "D5") (pin "2") (pinfunction "2_2") (pintype "passive"))
      (node (ref "R23") (pin "2") (pinfunction "2_2") (pintype "passive"))
      (node (ref "R26") (pin "2") (pinfunction "2_2") (pintype "passive"))
      (node (ref "R34") (pin "2") (pinfunction "2_2") (pintype "passive"))
      (node (ref "U3") (pin "1") (pinfunction "VM_1") (pintype "passive"))
      (node (ref "U4") (pin "2") (pinfunction "Vin_2") (pintype "passive"))
    )
    (net (code "58") (name "VCC") (class "Default")
      (node (ref "C12") (pin "1") (pinfunction "1_1") (pintype "passive"))
      (node (ref "C15") (pin "1") (pinfunction "1_1") (pintype "passive"))
      (node (ref "C20") (pin "2") (pinfunction "2_2") (pintype "passive"))
      (node (ref "C6") (pin "2") (pinfunction "2_2") (pintype "passive"))
      (node (ref "C7") (pin "2") (pinfunction "2_2") (pintype "passive"))
      (node (ref "C8") (pin "1") (pinfunction "1_1") (pintype "passive"))
      (node (ref "D1") (pin "1") (pinfunction "1_1") (pintype "passive"))
      (node (ref "D2") (pin "1") (pinfunction "1_1") (pintype "passive"))
      (node (ref "J1") (pin "5") (pinfunction "5_5") (pintype "passive"))
      (node (ref "Q5") (pin "2") (pinfunction "S_2") (pintype "passive"))
      (node (ref "R1") (pin "2") (pinfunction "2_2") (pintype "passive"))
      (node (ref "R18") (pin "2") (pinfunction "2_2") (pintype "passive"))
      (node (ref "R3") (pin "1") (pinfunction "1_1") (pintype "passive"))
      (node (ref "R34") (pin "1") (pinfunction "1_1") (pintype "passive"))
      (node (ref "R4") (pin "1") (pinfunction "1_1") (pintype "passive"))
      (node (ref "U1") (pin "64") (pinfunction "VDD(VDDA)_64") (pintype "passive"))
      (node (ref "U1") (pin "66") (pinfunction "VREFP_66") (pintype "passive"))
      (node (ref "U1") (pin "67") (pinfunction "VBAT_67") (pintype "passive"))
      (node (ref "U3") (pin "8") (pinfunction "VCC_8") (pintype "passive"))
      (node (ref "U4") (pin "3") (pinfunction "Vout_3") (pintype "passive"))
      (node (ref "V1") (pin "1") (pinfunction "1_1") (pintype "passive"))
    )
    (net (code "59") (name "VIN") (class "Default")
      (node (ref "D3") (pin "1") (pinfunction "1_1") (pintype "passive"))
      (node (ref "F1") (pin "2") (pinfunction "2_2") (pintype "passive"))
      (node (ref "Q1") (pin "2") (pinfunction "E_2") (pintype "passive"))
      (node (ref "R6") (pin "2") (pinfunction "2_2") (pintype "passive"))
      (node (ref "TVS1") (pin "2") (pinfunction "2_2") (pintype "passive"))
    )
    (net (code "60") (name "VIN1") (class "Default")
      (node (ref "F1") (pin "1") (pinfunction "1_1") (pintype "passive"))
      (node (ref "P1") (pin "2") (pinfunction "2_2") (pintype "passive"))
      (node (ref "P3") (pin "2") (pinfunction "2_2") (pintype "passive"))
      (node (ref "VIN1") (pin "1") (pinfunction "1_1") (pintype "passive"))
    )
    (net (code "61") (name "unconnected-(K2-Pad2)") (class "Default")
      (node (ref "K2") (pin "2") (pinfunction "2_2") (pintype "passive"))
    )
    (net (code "62") (name "unconnected-(K2-Pad3)") (class "Default")
      (node (ref "K2") (pin "3") (pinfunction "3_3") (pintype "passive"))
    )
    (net (code "63") (name "unconnected-(K2-Pad4)") (class "Default")
      (node (ref "K2") (pin "4") (pinfunction "4_4") (pintype "passive"))
    )
    (net (code "64") (name "unconnected-(K2-Pad7)") (class "Default")
      (node (ref "K2") (pin "7") (pinfunction "7_7") (pintype "passive"))
    )
    (net (code "65") (name "unconnected-(U1-PA0{slash}COM0{slash}UART4_RX{slash}ADC_IN5{slash}LUT3_OUT-Pad6)") (class "Default")
      (node (ref "U1") (pin "6") (pinfunction "PA0/COM0/UART4_RX/ADC_IN5/LUT3_OUT_6") (pintype "passive"))
    )
    (net (code "66") (name "unconnected-(U1-PA1{slash}COM1{slash}UART4_TX{slash}ADC_IN12{slash}LUT2_OUT-Pad7)") (class "Default")
      (node (ref "U1") (pin "7") (pinfunction "PA1/COM1/UART4_TX/ADC_IN12/LUT2_OUT_7") (pintype "passive"))
    )
    (net (code "67") (name "unconnected-(U1-PA4{slash}COM4{slash}SEG28{slash}GPT1_CH3{slash}COMP2_INN1-Pad10)") (class "Default")
      (node (ref "U1") (pin "10") (pinfunction "PA4/COM4/SEG28/GPT1_CH3/COMP2_INN1_10") (pintype "passive"))
    )
    (net (code "68") (name "unconnected-(U1-PA5{slash}COM5{slash}SEG29{slash}GPT1_CH4{slash}COMP2_INN2-Pad11)") (class "Default")
      (node (ref "U1") (pin "11") (pinfunction "PA5/COM5/SEG29/GPT1_CH4/COMP2_INN2_11") (pintype "passive"))
    )
    (net (code "69") (name "unconnected-(U1-PA7{slash}COM7{slash}SEG31{slash}OPA1_INP2{slash}CAN_TX-Pad13)") (class "Default")
      (node (ref "U1") (pin "13") (pinfunction "PA7/COM7/SEG31/OPA1_INP2/CAN_TX_13") (pintype "passive"))
    )
    (net (code "70") (name "unconnected-(U1-PA11{slash}SEG32{slash}SCL0{slash}LPUART2_RX-Pad17)") (class "Default")
      (node (ref "U1") (pin "17") (pinfunction "PA11/SEG32/SCL0/LPUART2_RX_17") (pintype "passive"))
    )
    (net (code "71") (name "unconnected-(U1-PA12{slash}SEG33{slash}SDA0{slash}LPUART2_TX-Pad18)") (class "Default")
      (node (ref "U1") (pin "18") (pinfunction "PA12/SEG33/SDA0/LPUART2_TX_18") (pintype "passive"))
    )
    (net (code "72") (name "unconnected-(U1-PB0{slash}SEG34{slash}UART3_RX{slash}SPI1_MISO{slash}OPA1_OUT3-Pad21)") (class "Default")
      (node (ref "U1") (pin "21") (pinfunction "PB0/SEG34/UART3_RX/SPI1_MISO/OPA1_OUT3_21") (pintype "passive"))
    )
    (net (code "73") (name "unconnected-(U1-PB1{slash}SEG35{slash}UART3_TX{slash}SPI1_MOSI{slash}OPA1_OUT4-Pad22)") (class "Default")
      (node (ref "U1") (pin "22") (pinfunction "PB1/SEG35/UART3_TX/SPI1_MOSI/OPA1_OUT4_22") (pintype "passive"))
    )
    (net (code "74") (name "unconnected-(U1-PB2(WKUP2){slash}VCIN1{slash}UART4_RX{slash}ATIM_CHIN-Pad23)") (class "Default")
      (node (ref "U1") (pin "23") (pinfunction "PB2(WKUP2)/VCIN1/UART4_RX/ATIM_CHIN_23") (pintype "passive"))
    )
    (net (code "75") (name "unconnected-(U1-PB3{slash}VCIN2{slash}UART4_TX{slash}ATIM_CH2N-Pad24)") (class "Default")
      (node (ref "U1") (pin "24") (pinfunction "PB3/VCIN2/UART4_TX/ATIM_CH2N_24") (pintype "passive"))
    )
    (net (code "76") (name "unconnected-(U1-PB4{slash}SEG3{slash}ATIM_CH1{slash}LPUART2_RX{slash}COMP3_INN1-Pad25)") (class "Default")
      (node (ref "U1") (pin "25") (pinfunction "PB4/SEG3/ATIM_CH1/LPUART2_RX/COMP3_INN1_25") (pintype "passive"))
    )
    (net (code "77") (name "unconnected-(U1-PB5{slash}SEG4{slash}ATIM_CH2{slash}LPUART2_TX{slash}COMP3_INN2-Pad26)") (class "Default")
      (node (ref "U1") (pin "26") (pinfunction "PB5/SEG4/ATIM_CH2/LPUART2_TX/COMP3_INN2_26") (pintype "passive"))
    )
    (net (code "78") (name "unconnected-(U1-PB6{slash}SEG5{slash}ATIM_CH3{slash}SPI2_SSN-Pad27)") (class "Default")
      (node (ref "U1") (pin "27") (pinfunction "PB6/SEG5/ATIM_CH3/SPI2_SSN_27") (pintype "passive"))
    )
    (net (code "79") (name "unconnected-(U1-PB7{slash}SEG6{slash}ATIM_CH4{slash}SPI2_SCK{slash}ANATST-Pad28)") (class "Default")
      (node (ref "U1") (pin "28") (pinfunction "PB7/SEG6/ATIM_CH4/SPI2_SCK/ANATST_28") (pintype "passive"))
    )
    (net (code "80") (name "unconnected-(U1-PB8{slash}SEG7{slash}SPI0_SSN{slash}ATIM_CH3N{slash}COMP1_INP1-Pad29)") (class "Default")
      (node (ref "U1") (pin "29") (pinfunction "PB8/SEG7/SPI0_SSN/ATIM_CH3N/COMP1_INP1_29") (pintype "passive"))
    )
    (net (code "81") (name "unconnected-(U1-PB9{slash}SEG8{slash}SPI0_SCK{slash}GPT0_ETR{slash}COMP1_INP2-Pad30)") (class "Default")
      (node (ref "U1") (pin "30") (pinfunction "PB9/SEG8/SPI0_SCK/GPT0_ETR/COMP1_INP2_30") (pintype "passive"))
    )
    (net (code "82") (name "unconnected-(U1-PB10{slash}SEG9{slash}SPI0_MISO{slash}GPT0_CH1{slash}OPA1_INN1-Pad31)") (class "Default")
      (node (ref "U1") (pin "31") (pinfunction "PB10/SEG9/SPI0_MISO/GPT0_CH1/OPA1_INN1_31") (pintype "passive"))
    )
    (net (code "83") (name "unconnected-(U1-PB11{slash}SEG10{slash}SPI0_MOSI{slash}GPT0_CH2{slash}OPA1_INP1-Pad32)") (class "Default")
      (node (ref "U1") (pin "32") (pinfunction "PB11/SEG10/SPI0_MOSI/GPT0_CH2/OPA1_INP1_32") (pintype "passive"))
    )
    (net (code "84") (name "unconnected-(U1-PB15{slash}VDISP0{slash}SCL1{slash}SPI2_MISO-Pad44)") (class "Default")
      (node (ref "U1") (pin "44") (pinfunction "PB15/VDISP0/SCL1/SPI2_MISO_44") (pintype "passive"))
    )
    (net (code "85") (name "unconnected-(U1-PC0{slash}VDISP2{slash}GPT1_CH1{slash}COMP3_INP1{slash}LUT0_OUT-Pad46)") (class "Default")
      (node (ref "U1") (pin "46") (pinfunction "PC0/VDISP2/GPT1_CH1/COMP3_INP1/LUT0_OUT_46") (pintype "passive"))
    )
    (net (code "86") (name "unconnected-(U1-PC1{slash}VDISP3{slash}GPT1_CH2{slash}COMP3_INP2{slash}LUT1_OUT-Pad47)") (class "Default")
      (node (ref "U1") (pin "47") (pinfunction "PC1/VDISP3/GPT1_CH2/COMP3_INP2/LUT1_OUT_47") (pintype "passive"))
    )
    (net (code "87") (name "unconnected-(U1-PC2{slash}XTHIN{slash}UART1_RX{slash}LPUART1_RX-Pad48)") (class "Default")
      (node (ref "U1") (pin "48") (pinfunction "PC2/XTHIN/UART1_RX/LPUART1_RX_48") (pintype "passive"))
    )
    (net (code "88") (name "unconnected-(U1-PC3{slash}XTHOUT{slash}UART1_TX{slash}LPUART1_TX-Pad49)") (class "Default")
      (node (ref "U1") (pin "49") (pinfunction "PC3/XTHOUT/UART1_TX/LPUART1_TX_49") (pintype "passive"))
    )
    (net (code "89") (name "unconnected-(U1-PC4{slash}SEG13{slash}UART5_RX{slash}COMP1_OUT{slash}OPA1_OUT2-Pad50)") (class "Default")
      (node (ref "U1") (pin "50") (pinfunction "PC4/SEG13/UART5_RX/COMP1_OUT/OPA1_OUT2_50") (pintype "passive"))
    )
    (net (code "90") (name "unconnected-(U1-PC5{slash}SEG14{slash}UART5_TX{slash}COMP2_OUT{slash}DAC_OUT-Pad51)") (class "Default")
      (node (ref "U1") (pin "51") (pinfunction "PC5/SEG14/UART5_TX/COMP2_OUT/DAC_OUT_51") (pintype "passive"))
    )
    (net (code "91") (name "unconnected-(U1-PC6(WKUP4){slash}SEG15{slash}COMP1_INN2{slash}GPT1_ETR-Pad52)") (class "Default")
      (node (ref "U1") (pin "52") (pinfunction "PC6(WKUP4)/SEG15/COMP1_INN2/GPT1_ETR_52") (pintype "passive"))
    )
    (net (code "92") (name "unconnected-(U1-PC13{slash}SEG40{slash}U7816CLK{slash}LPT16_CH1-Pad40)") (class "Default")
      (node (ref "U1") (pin "40") (pinfunction "PC13/SEG40/U7816CLK/LPT16_CH1_40") (pintype "passive"))
    )
    (net (code "93") (name "unconnected-(U1-PC14{slash}SEG41{slash}U7816IO{slash}LPT16_CH2-Pad41)") (class "Default")
      (node (ref "U1") (pin "41") (pinfunction "PC14/SEG41/U7816IO/LPT16_CH2_41") (pintype "passive"))
    )
    (net (code "94") (name "unconnected-(U1-PC15{slash}SEG42{slash}LPT32_CH3{slash}CAN_RX-Pad42)") (class "Default")
      (node (ref "U1") (pin "42") (pinfunction "PC15/SEG42/LPT32_CH3/CAN_RX_42") (pintype "passive"))
    )
    (net (code "95") (name "unconnected-(U1-PD0{slash}SEG22{slash}UART5_RX{slash}ADC_IN7{slash}GPT2_CH1-Pad71)") (class "Default")
      (node (ref "U1") (pin "71") (pinfunction "PD0/SEG22/UART5_RX/ADC_IN7/GPT2_CH1_71") (pintype "passive"))
    )
    (net (code "96") (name "unconnected-(U1-PD1{slash}SEG23{slash}UART5_TX{slash}ADC_IN1{slash}GPT2_CH2-Pad72)") (class "Default")
      (node (ref "U1") (pin "72") (pinfunction "PD1/SEG23/UART5_TX/ADC_IN1/GPT2_CH2_72") (pintype "passive"))
    )
    (net (code "97") (name "unconnected-(U1-PD2{slash}SEG24{slash}SPI1_SSN{slash}ADC_IN8{slash}GPT2_CH3-Pad73)") (class "Default")
      (node (ref "U1") (pin "73") (pinfunction "PD2/SEG24/SPI1_SSN/ADC_IN8/GPT2_CH3_73") (pintype "passive"))
    )
    (net (code "98") (name "unconnected-(U1-PD3{slash}SEG25{slash}SPI1_SCK{slash}ADC_IN2{slash}GPT2_CH4-Pad74)") (class "Default")
      (node (ref "U1") (pin "74") (pinfunction "PD3/SEG25/SPI1_SCK/ADC_IN2/GPT2_CH4_74") (pintype "passive"))
    )
    (net (code "99") (name "unconnected-(U1-PD4{slash}SEG26{slash}SPI1_MISO{slash}ADC_IN9{slash}GPT2_ETR-Pad75)") (class "Default")
      (node (ref "U1") (pin "75") (pinfunction "PD4/SEG26/SPI1_MISO/ADC_IN9/GPT2_ETR_75") (pintype "passive"))
    )
    (net (code "100") (name "unconnected-(U1-PD5{slash}SEG27{slash}SPI1_MOSI{slash}ADC_IN3{slash}LPT16_ETR-Pad76)") (class "Default")
      (node (ref "U1") (pin "76") (pinfunction "PD5/SEG27/SPI1_MOSI/ADC_IN3/LPT16_ETR_76") (pintype "passive"))
    )
    (net (code "101") (name "unconnected-(U1-PD9(WKUP8)-Pad19)") (class "Default")
      (node (ref "U1") (pin "19") (pinfunction "PD9(WKUP8)_19") (pintype "passive"))
    )
    (net (code "102") (name "unconnected-(U1-PD11(WKUP6){slash}FOUT0{slash}ADC_IN0{slash}ATIM_BRK1-Pad70)") (class "Default")
      (node (ref "U1") (pin "70") (pinfunction "PD11(WKUP6)/FOUT0/ADC_IN0/ATIM_BRK1_70") (pintype "passive"))
    )
    (net (code "103") (name "unconnected-(U1-PD12{slash}VDISP1{slash}SDA1{slash}SPI2_MOSI-Pad45)") (class "Default")
      (node (ref "U1") (pin "45") (pinfunction "PD12/VDISP1/SDA1/SPI2_MOSI_45") (pintype "passive"))
    )
    (net (code "104") (name "unconnected-(U1-PE0{slash}SEG36{slash}SPI0_SSN-Pad36)") (class "Default")
      (node (ref "U1") (pin "36") (pinfunction "PE0/SEG36/SPI0_SSN_36") (pintype "passive"))
    )
    (net (code "105") (name "unconnected-(U1-PE1{slash}SEG37{slash}SPI0_SCK-Pad37)") (class "Default")
      (node (ref "U1") (pin "37") (pinfunction "PE1/SEG37/SPI0_SCK_37") (pintype "passive"))
    )
    (net (code "106") (name "unconnected-(U1-PE2{slash}SEG38{slash}SPI0_MISO-Pad38)") (class "Default")
      (node (ref "U1") (pin "38") (pinfunction "PE2/SEG38/SPI0_MISO_38") (pintype "passive"))
    )
    (net (code "107") (name "unconnected-(U1-PE3{slash}SEG39{slash}SPI0_MOSI-Pad39)") (class "Default")
      (node (ref "U1") (pin "39") (pinfunction "PE3/SEG39/SPI0_MOSI_39") (pintype "passive"))
    )
    (net (code "108") (name "unconnected-(U1-PE5{slash}SEG43{slash}LPT32_CH4{slash}CAN_TX-Pad43)") (class "Default")
      (node (ref "U1") (pin "43") (pinfunction "PE5/SEG43/LPT32_CH4/CAN_TX_43") (pintype "passive"))
    )
    (net (code "109") (name "unconnected-(U1-PE6(WKUP9)-Pad68)") (class "Default")
      (node (ref "U1") (pin "68") (pinfunction "PE6(WKUP9)_68") (pintype "passive"))
    )
    (net (code "110") (name "unconnected-(U1-PE7{slash}COMP3_OUT-Pad69)") (class "Default")
      (node (ref "U1") (pin "69") (pinfunction "PE7/COMP3_OUT_69") (pintype "passive"))
    )
    (net (code "111") (name "unconnected-(U1-PE8-Pad20)") (class "Default")
      (node (ref "U1") (pin "20") (pinfunction "PE8_20") (pintype "passive"))
    )
    (net (code "112") (name "unconnected-(U1-PH15{slash}RTCOUT{slash}TAMPER-Pad59)") (class "Default")
      (node (ref "U1") (pin "59") (pinfunction "PH15/RTCOUT/TAMPER_59") (pintype "passive"))
    )
    (net (code "113") (name "unconnected-(U2-Pad39)") (class "Default")
      (node (ref "U2") (pin "39") (pinfunction "39_39") (pintype "passive"))
    )
    (net (code "114") (name "unconnected-(U2A-ANT-Pad27)") (class "Default")
      (node (ref "U2") (pin "27") (pinfunction "ANT_27") (pintype "passive"))
    )
    (net (code "115") (name "unconnected-(U2A-GND-Pad2)") (class "Default")
      (node (ref "U2") (pin "2") (pinfunction "GND_2") (pintype "passive"))
    )
    (net (code "116") (name "unconnected-(U2A-GND-Pad26)") (class "Default")
      (node (ref "U2") (pin "26") (pinfunction "GND_26") (pintype "passive"))
    )
    (net (code "117") (name "unconnected-(U2A-MIC_LDO-Pad1)") (class "Default")
      (node (ref "U2") (pin "1") (pinfunction "MIC_LDO_1") (pintype "passive"))
    )
    (net (code "118") (name "unconnected-(U2A-REV-Pad3)") (class "Default")
      (node (ref "U2") (pin "3") (pinfunction "REV_3") (pintype "passive"))
    )
    (net (code "119") (name "unconnected-(U2A-REV-Pad4)") (class "Default")
      (node (ref "U2") (pin "4") (pinfunction "REV_4") (pintype "passive"))
    )
    (net (code "120") (name "unconnected-(U2A-REV-Pad5)") (class "Default")
      (node (ref "U2") (pin "5") (pinfunction "REV_5") (pintype "passive"))
    )
    (net (code "121") (name "unconnected-(U2A-REV-Pad19)") (class "Default")
      (node (ref "U2") (pin "19") (pinfunction "REV_19") (pintype "passive"))
    )
    (net (code "122") (name "unconnected-(U2A-REV-Pad20)") (class "Default")
      (node (ref "U2") (pin "20") (pinfunction "REV_20") (pintype "passive"))
    )
    (net (code "123") (name "unconnected-(U2A-SWCLK-Pad13)") (class "Default")
      (node (ref "U2") (pin "13") (pinfunction "SWCLK_13") (pintype "passive"))
    )
    (net (code "124") (name "unconnected-(U2A-SWDIO-Pad14)") (class "Default")
      (node (ref "U2") (pin "14") (pinfunction "SWDIO_14") (pintype "passive"))
    )
    (net (code "125") (name "unconnected-(U2A-TEST_IO-Pad9)") (class "Default")
      (node (ref "U2") (pin "9") (pinfunction "TEST_IO_9") (pintype "passive"))
    )
    (net (code "126") (name "unconnected-(U2A-UART_L1_RXD-Pad8)") (class "Default")
      (node (ref "U2") (pin "8") (pinfunction "UART_L1_RXD_8") (pintype "passive"))
    )
    (net (code "127") (name "unconnected-(U2A-UART_L1_TXD-Pad7)") (class "Default")
      (node (ref "U2") (pin "7") (pinfunction "UART_L1_TXD_7") (pintype "passive"))
    )
    (net (code "128") (name "unconnected-(U2A-USB_DN-Pad16)") (class "Default")
      (node (ref "U2") (pin "16") (pinfunction "USB_DN_16") (pintype "passive"))
    )
    (net (code "129") (name "unconnected-(U2A-USB_DP-Pad15)") (class "Default")
      (node (ref "U2") (pin "15") (pinfunction "USB_DP_15") (pintype "passive"))
    )
    (net (code "130") (name "unconnected-(U2B-ANT_TP-Pad32)") (class "Default")
      (node (ref "U2") (pin "32") (pinfunction "ANT_TP_32") (pintype "passive"))
    )
    (net (code "131") (name "unconnected-(U2B-GND_TP-Pad33)") (class "Default")
      (node (ref "U2") (pin "33") (pinfunction "GND_TP_33") (pintype "passive"))
    )
    (net (code "132") (name "unconnected-(U2B-NC-Pad28)") (class "Default")
      (node (ref "U2") (pin "28") (pinfunction "NC_28") (pintype "passive"))
    )
    (net (code "133") (name "unconnected-(U2B-NC-Pad44)") (class "Default")
      (node (ref "U2") (pin "44") (pinfunction "NC_44") (pintype "passive"))
    )
    (net (code "134") (name "unconnected-(U2B-NC-Pad45)") (class "Default")
      (node (ref "U2") (pin "45") (pinfunction "NC_45") (pintype "passive"))
    )
    (net (code "135") (name "unconnected-(U2B-REV-Pad34)") (class "Default")
      (node (ref "U2") (pin "34") (pinfunction "REV_34") (pintype "passive"))
    )
    (net (code "136") (name "unconnected-(U2B-REV-Pad35)") (class "Default")
      (node (ref "U2") (pin "35") (pinfunction "REV_35") (pintype "passive"))
    )
    (net (code "137") (name "unconnected-(U2B-REV-Pad36)") (class "Default")
      (node (ref "U2") (pin "36") (pinfunction "REV_36") (pintype "passive"))
    )
    (net (code "138") (name "unconnected-(U2B-REV-Pad37)") (class "Default")
      (node (ref "U2") (pin "37") (pinfunction "REV_37") (pintype "passive"))
    )
    (net (code "139") (name "unconnected-(U2B-REV-Pad40)") (class "Default")
      (node (ref "U2") (pin "40") (pinfunction "REV_40") (pintype "passive"))
    )
    (net (code "140") (name "unconnected-(U2B-REV-Pad41)") (class "Default")
      (node (ref "U2") (pin "41") (pinfunction "REV_41") (pintype "passive"))
    )
    (net (code "141") (name "unconnected-(U2B-REV-Pad43)") (class "Default")
      (node (ref "U2") (pin "43") (pinfunction "REV_43") (pintype "passive"))
    )
    (net (code "142") (name "unconnected-(U2B-REV-Pad46)") (class "Default")
      (node (ref "U2") (pin "46") (pinfunction "REV_46") (pintype "passive"))
    )
    (net (code "143") (name "unconnected-(U2B-REV-Pad47)") (class "Default")
      (node (ref "U2") (pin "47") (pinfunction "REV_47") (pintype "passive"))
    )
    (net (code "144") (name "unconnected-(U2B-TEST_IO-Pad42)") (class "Default")
      (node (ref "U2") (pin "42") (pinfunction "TEST_IO_42") (pintype "passive"))
    )
  )
)
